# tenere-controller-rev-C.net
KiCad netlist of a schematic drawn in EAGLE
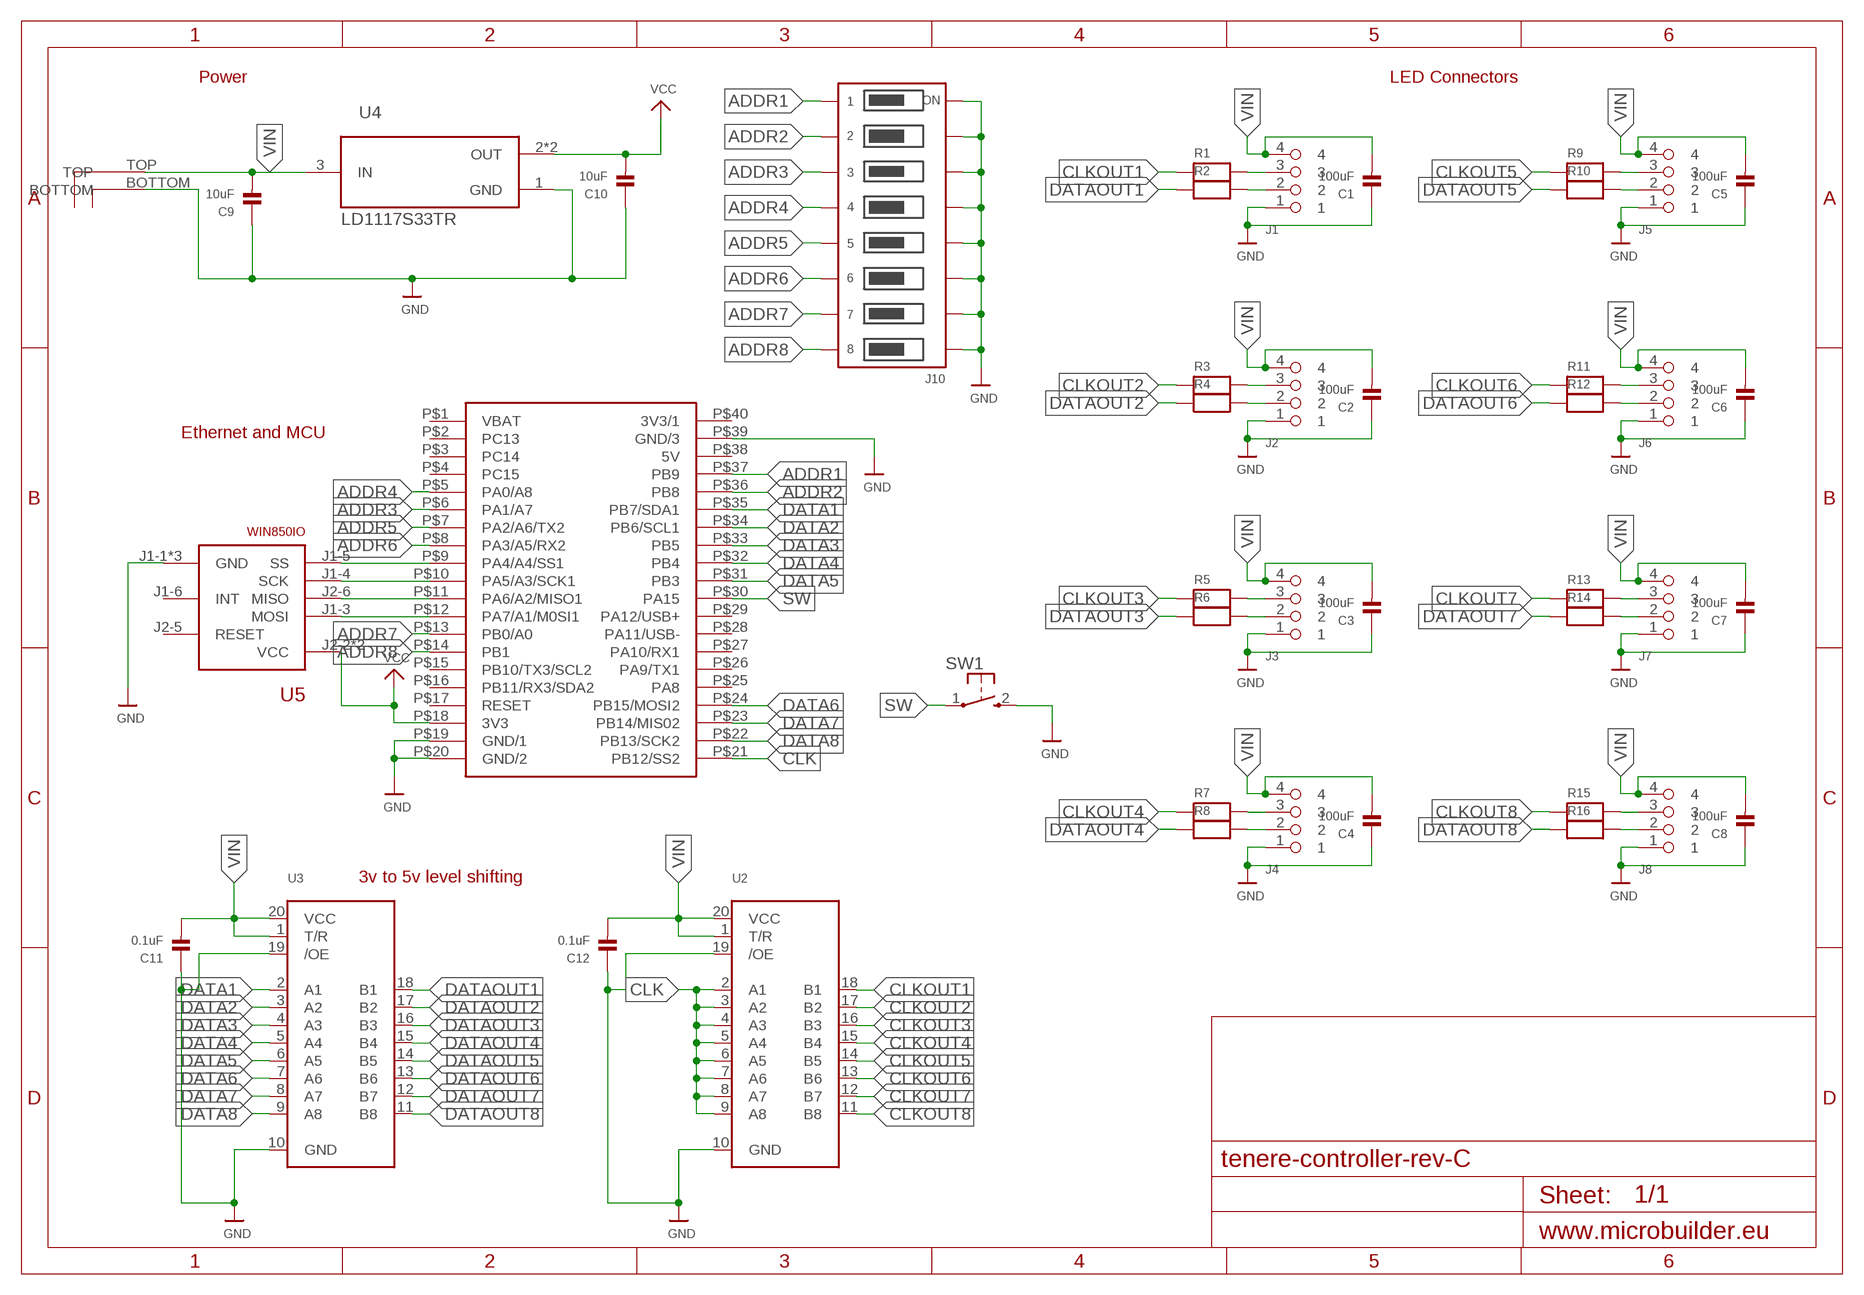
[diagram p0: schematic, sheet 1]

(export (version "E")
  (design (tool "Eeschema 10.0.6"))
  (components
    (comp (ref "C1")
      (value "100uF")
      (footprint "eagle-import:1206")
      (libsource (lib "eagle-import") (part "CAP_CERAMIC1206"))
    )
    (comp (ref "C2")
      (value "100uF")
      (footprint "eagle-import:1206")
      (libsource (lib "eagle-import") (part "CAP_CERAMIC1206"))
    )
    (comp (ref "C3")
      (value "100uF")
      (footprint "eagle-import:1206")
      (libsource (lib "eagle-import") (part "CAP_CERAMIC1206"))
    )
    (comp (ref "C4")
      (value "100uF")
      (footprint "eagle-import:1206")
      (libsource (lib "eagle-import") (part "CAP_CERAMIC1206"))
    )
    (comp (ref "C5")
      (value "100uF")
      (footprint "eagle-import:1206")
      (libsource (lib "eagle-import") (part "CAP_CERAMIC1206"))
    )
    (comp (ref "C6")
      (value "100uF")
      (footprint "eagle-import:1206")
      (libsource (lib "eagle-import") (part "CAP_CERAMIC1206"))
    )
    (comp (ref "C7")
      (value "100uF")
      (footprint "eagle-import:1206")
      (libsource (lib "eagle-import") (part "CAP_CERAMIC1206"))
    )
    (comp (ref "C8")
      (value "100uF")
      (footprint "eagle-import:1206")
      (libsource (lib "eagle-import") (part "CAP_CERAMIC1206"))
    )
    (comp (ref "C9")
      (value "10uF")
      (footprint "eagle-import:0603")
      (libsource (lib "eagle-import") (part "CAP_CERAMIC0603"))
    )
    (comp (ref "C10")
      (value "10uF")
      (footprint "eagle-import:0603")
      (libsource (lib "eagle-import") (part "CAP_CERAMIC0603"))
    )
    (comp (ref "C11")
      (value "0.1uF")
      (footprint "eagle-import:0603")
      (libsource (lib "eagle-import") (part "CAP_CERAMIC0603"))
    )
    (comp (ref "C12")
      (value "0.1uF")
      (footprint "eagle-import:0603")
      (libsource (lib "eagle-import") (part "CAP_CERAMIC0603"))
    )
    (comp (ref "J1")
      (value "MICROFIT3")
      (footprint "eagle-import:43650-0400")
      (libsource (lib "eagle-import") (part "MICROFIT3"))
    )
    (comp (ref "J2")
      (value "MICROFIT3")
      (footprint "eagle-import:43650-0400")
      (libsource (lib "eagle-import") (part "MICROFIT3"))
    )
    (comp (ref "J3")
      (value "MICROFIT3")
      (footprint "eagle-import:43650-0400")
      (libsource (lib "eagle-import") (part "MICROFIT3"))
    )
    (comp (ref "J4")
      (value "MICROFIT3")
      (footprint "eagle-import:43650-0400")
      (libsource (lib "eagle-import") (part "MICROFIT3"))
    )
    (comp (ref "J5")
      (value "MICROFIT3")
      (footprint "eagle-import:43650-0400")
      (libsource (lib "eagle-import") (part "MICROFIT3"))
    )
    (comp (ref "J6")
      (value "MICROFIT3")
      (footprint "eagle-import:43650-0400")
      (libsource (lib "eagle-import") (part "MICROFIT3"))
    )
    (comp (ref "J7")
      (value "MICROFIT3")
      (footprint "eagle-import:43650-0400")
      (libsource (lib "eagle-import") (part "MICROFIT3"))
    )
    (comp (ref "J8")
      (value "MICROFIT3")
      (footprint "eagle-import:43650-0400")
      (libsource (lib "eagle-import") (part "MICROFIT3"))
    )
    (comp (ref "J9")
      (value "POWERPOLE-2V")
      (footprint "eagle-import:POWERPOLE_STACKED")
      (libsource (lib "eagle-import") (part "POWERPOLE-2V"))
    )
    (comp (ref "J10")
      (value "DIP-SWITCH-8PIN")
      (footprint "eagle-import:BPA08B")
      (libsource (lib "eagle-import") (part "DIP-SWITCH-8PIN"))
    )
    (comp (ref "R1")
      (value "RESISTOR0603")
      (footprint "eagle-import:0603")
      (libsource (lib "eagle-import") (part "RESISTOR0603"))
    )
    (comp (ref "R2")
      (value "RESISTOR0603")
      (footprint "eagle-import:0603")
      (libsource (lib "eagle-import") (part "RESISTOR0603"))
    )
    (comp (ref "R3")
      (value "RESISTOR0603")
      (footprint "eagle-import:0603")
      (libsource (lib "eagle-import") (part "RESISTOR0603"))
    )
    (comp (ref "R4")
      (value "RESISTOR0603")
      (footprint "eagle-import:0603")
      (libsource (lib "eagle-import") (part "RESISTOR0603"))
    )
    (comp (ref "R5")
      (value "RESISTOR0603")
      (footprint "eagle-import:0603")
      (libsource (lib "eagle-import") (part "RESISTOR0603"))
    )
    (comp (ref "R6")
      (value "RESISTOR0603")
      (footprint "eagle-import:0603")
      (libsource (lib "eagle-import") (part "RESISTOR0603"))
    )
    (comp (ref "R7")
      (value "RESISTOR0603")
      (footprint "eagle-import:0603")
      (libsource (lib "eagle-import") (part "RESISTOR0603"))
    )
    (comp (ref "R8")
      (value "RESISTOR0603")
      (footprint "eagle-import:0603")
      (libsource (lib "eagle-import") (part "RESISTOR0603"))
    )
    (comp (ref "R9")
      (value "RESISTOR0603")
      (footprint "eagle-import:0603")
      (libsource (lib "eagle-import") (part "RESISTOR0603"))
    )
    (comp (ref "R10")
      (value "RESISTOR0603")
      (footprint "eagle-import:0603")
      (libsource (lib "eagle-import") (part "RESISTOR0603"))
    )
    (comp (ref "R11")
      (value "RESISTOR0603")
      (footprint "eagle-import:0603")
      (libsource (lib "eagle-import") (part "RESISTOR0603"))
    )
    (comp (ref "R12")
      (value "RESISTOR0603")
      (footprint "eagle-import:0603")
      (libsource (lib "eagle-import") (part "RESISTOR0603"))
    )
    (comp (ref "R13")
      (value "RESISTOR0603")
      (footprint "eagle-import:0603")
      (libsource (lib "eagle-import") (part "RESISTOR0603"))
    )
    (comp (ref "R14")
      (value "RESISTOR0603")
      (footprint "eagle-import:0603")
      (libsource (lib "eagle-import") (part "RESISTOR0603"))
    )
    (comp (ref "R15")
      (value "RESISTOR0603")
      (footprint "eagle-import:0603")
      (libsource (lib "eagle-import") (part "RESISTOR0603"))
    )
    (comp (ref "R16")
      (value "RESISTOR0603")
      (footprint "eagle-import:0603")
      (libsource (lib "eagle-import") (part "RESISTOR0603"))
    )
    (comp (ref "SW1")
      (value "TACTILE-SWITCH-1825027")
      (footprint "eagle-import:1825027")
      (libsource (lib "eagle-import") (part "TACTILE-SWITCH-1825027"))
    )
    (comp (ref "U1")
      (value "BLUEPILL")
      (footprint "eagle-import:40-DIP-BLUE-PIL")
      (libsource (lib "eagle-import") (part "BLUEPILL"))
    )
    (comp (ref "U2")
      (value "74LCX245")
      (footprint "eagle-import:TSSOP20")
      (libsource (lib "eagle-import") (part "74LCX245"))
    )
    (comp (ref "U3")
      (value "74LCX245")
      (footprint "eagle-import:TSSOP20")
      (libsource (lib "eagle-import") (part "74LCX245"))
    )
    (comp (ref "U4")
      (value "LD1117S33TR")
      (footprint "eagle-import:LD1117S33TR_SOT230P700X180-4N")
      (fields (field (name "MANUFACTURER") "ST Microelectronics"))
      (libsource (lib "eagle-import") (part "LD1117S33TR"))
    )
    (comp (ref "U5")
      (value "WIN850IO")
      (footprint "eagle-import:WIZ850IO")
      (libsource (lib "eagle-import") (part "WIN850IO"))
    )
  )
  (nets
    (net (code "1") (name "ADDR1") (class "Default")
      (node (ref "J10") (pin "1'") (pinfunction "1B_1'") (pintype "bidirectional"))
      (node (ref "U1") (pin "P$37") (pinfunction "PB9_P$37") (pintype "bidirectional"))
    )
    (net (code "2") (name "ADDR2") (class "Default")
      (node (ref "J10") (pin "2'") (pinfunction "2B_2'") (pintype "bidirectional"))
      (node (ref "U1") (pin "P$36") (pinfunction "PB8_P$36") (pintype "bidirectional"))
    )
    (net (code "3") (name "ADDR3") (class "Default")
      (node (ref "J10") (pin "3'") (pinfunction "3B_3'") (pintype "bidirectional"))
      (node (ref "U1") (pin "P$6") (pinfunction "PA1/A7_P$6") (pintype "bidirectional"))
    )
    (net (code "4") (name "ADDR4") (class "Default")
      (node (ref "J10") (pin "4'") (pinfunction "4B_4'") (pintype "bidirectional"))
      (node (ref "U1") (pin "P$5") (pinfunction "PA0/A8_P$5") (pintype "bidirectional"))
    )
    (net (code "5") (name "ADDR5") (class "Default")
      (node (ref "J10") (pin "5'") (pinfunction "5B_5'") (pintype "bidirectional"))
      (node (ref "U1") (pin "P$7") (pinfunction "PA2/A6/TX2_P$7") (pintype "bidirectional"))
    )
    (net (code "6") (name "ADDR6") (class "Default")
      (node (ref "J10") (pin "6'") (pinfunction "6B_6'") (pintype "bidirectional"))
      (node (ref "U1") (pin "P$8") (pinfunction "PA3/A5/RX2_P$8") (pintype "bidirectional"))
    )
    (net (code "7") (name "ADDR7") (class "Default")
      (node (ref "J10") (pin "7'") (pinfunction "7B_7'") (pintype "bidirectional"))
      (node (ref "U1") (pin "P$13") (pinfunction "PB0/A0_P$13") (pintype "bidirectional"))
    )
    (net (code "8") (name "ADDR8") (class "Default")
      (node (ref "J10") (pin "8'") (pinfunction "8B_8'") (pintype "bidirectional"))
      (node (ref "U1") (pin "P$14") (pinfunction "PB1_P$14") (pintype "bidirectional"))
    )
    (net (code "9") (name "CLK") (class "Default")
      (node (ref "U1") (pin "P$21") (pinfunction "PB12/SS2_P$21") (pintype "bidirectional"))
      (node (ref "U2") (pin "2") (pinfunction "A1_2") (pintype "bidirectional"))
      (node (ref "U2") (pin "3") (pinfunction "A2_3") (pintype "bidirectional"))
      (node (ref "U2") (pin "4") (pinfunction "A3_4") (pintype "bidirectional"))
      (node (ref "U2") (pin "5") (pinfunction "A4_5") (pintype "bidirectional"))
      (node (ref "U2") (pin "6") (pinfunction "A5_6") (pintype "bidirectional"))
      (node (ref "U2") (pin "7") (pinfunction "A6_7") (pintype "bidirectional"))
      (node (ref "U2") (pin "8") (pinfunction "A7_8") (pintype "bidirectional"))
      (node (ref "U2") (pin "9") (pinfunction "A8_9") (pintype "bidirectional"))
    )
    (net (code "10") (name "CLKOUT1") (class "Default")
      (node (ref "R1") (pin "1") (pinfunction "1_1") (pintype "passive"))
      (node (ref "U2") (pin "18") (pinfunction "B1_18") (pintype "bidirectional"))
    )
    (net (code "11") (name "CLKOUT2") (class "Default")
      (node (ref "R3") (pin "1") (pinfunction "1_1") (pintype "passive"))
      (node (ref "U2") (pin "17") (pinfunction "B2_17") (pintype "bidirectional"))
    )
    (net (code "12") (name "CLKOUT3") (class "Default")
      (node (ref "R5") (pin "1") (pinfunction "1_1") (pintype "passive"))
      (node (ref "U2") (pin "16") (pinfunction "B3_16") (pintype "bidirectional"))
    )
    (net (code "13") (name "CLKOUT4") (class "Default")
      (node (ref "R7") (pin "1") (pinfunction "1_1") (pintype "passive"))
      (node (ref "U2") (pin "15") (pinfunction "B4_15") (pintype "bidirectional"))
    )
    (net (code "14") (name "CLKOUT5") (class "Default")
      (node (ref "R9") (pin "1") (pinfunction "1_1") (pintype "passive"))
      (node (ref "U2") (pin "14") (pinfunction "B5_14") (pintype "bidirectional"))
    )
    (net (code "15") (name "CLKOUT6") (class "Default")
      (node (ref "R11") (pin "1") (pinfunction "1_1") (pintype "passive"))
      (node (ref "U2") (pin "13") (pinfunction "B6_13") (pintype "bidirectional"))
    )
    (net (code "16") (name "CLKOUT7") (class "Default")
      (node (ref "R13") (pin "1") (pinfunction "1_1") (pintype "passive"))
      (node (ref "U2") (pin "12") (pinfunction "B7_12") (pintype "bidirectional"))
    )
    (net (code "17") (name "CLKOUT8") (class "Default")
      (node (ref "R15") (pin "1") (pinfunction "1_1") (pintype "passive"))
      (node (ref "U2") (pin "11") (pinfunction "B8_11") (pintype "bidirectional"))
    )
    (net (code "18") (name "DATA1") (class "Default")
      (node (ref "U1") (pin "P$35") (pinfunction "PB7/SDA1_P$35") (pintype "bidirectional"))
      (node (ref "U3") (pin "2") (pinfunction "A1_2") (pintype "bidirectional"))
    )
    (net (code "19") (name "DATA2") (class "Default")
      (node (ref "U1") (pin "P$34") (pinfunction "PB6/SCL1_P$34") (pintype "bidirectional"))
      (node (ref "U3") (pin "3") (pinfunction "A2_3") (pintype "bidirectional"))
    )
    (net (code "20") (name "DATA3") (class "Default")
      (node (ref "U1") (pin "P$33") (pinfunction "PB5_P$33") (pintype "bidirectional"))
      (node (ref "U3") (pin "4") (pinfunction "A3_4") (pintype "bidirectional"))
    )
    (net (code "21") (name "DATA4") (class "Default")
      (node (ref "U1") (pin "P$32") (pinfunction "PB4_P$32") (pintype "bidirectional"))
      (node (ref "U3") (pin "5") (pinfunction "A4_5") (pintype "bidirectional"))
    )
    (net (code "22") (name "DATA5") (class "Default")
      (node (ref "U1") (pin "P$31") (pinfunction "PB3_P$31") (pintype "bidirectional"))
      (node (ref "U3") (pin "6") (pinfunction "A5_6") (pintype "bidirectional"))
    )
    (net (code "23") (name "DATA6") (class "Default")
      (node (ref "U1") (pin "P$24") (pinfunction "PB15/MOSI2_P$24") (pintype "bidirectional"))
      (node (ref "U3") (pin "7") (pinfunction "A6_7") (pintype "bidirectional"))
    )
    (net (code "24") (name "DATA7") (class "Default")
      (node (ref "U1") (pin "P$23") (pinfunction "PB14/MIS02_P$23") (pintype "bidirectional"))
      (node (ref "U3") (pin "8") (pinfunction "A7_8") (pintype "bidirectional"))
    )
    (net (code "25") (name "DATA8") (class "Default")
      (node (ref "U1") (pin "P$22") (pinfunction "PB13/SCK2_P$22") (pintype "bidirectional"))
      (node (ref "U3") (pin "9") (pinfunction "A8_9") (pintype "bidirectional"))
    )
    (net (code "26") (name "DATAOUT1") (class "Default")
      (node (ref "R2") (pin "1") (pinfunction "1_1") (pintype "passive"))
      (node (ref "U3") (pin "18") (pinfunction "B1_18") (pintype "bidirectional"))
    )
    (net (code "27") (name "DATAOUT2") (class "Default")
      (node (ref "R4") (pin "1") (pinfunction "1_1") (pintype "passive"))
      (node (ref "U3") (pin "17") (pinfunction "B2_17") (pintype "bidirectional"))
    )
    (net (code "28") (name "DATAOUT3") (class "Default")
      (node (ref "R6") (pin "1") (pinfunction "1_1") (pintype "passive"))
      (node (ref "U3") (pin "16") (pinfunction "B3_16") (pintype "bidirectional"))
    )
    (net (code "29") (name "DATAOUT4") (class "Default")
      (node (ref "R8") (pin "1") (pinfunction "1_1") (pintype "passive"))
      (node (ref "U3") (pin "15") (pinfunction "B4_15") (pintype "bidirectional"))
    )
    (net (code "30") (name "DATAOUT5") (class "Default")
      (node (ref "R10") (pin "1") (pinfunction "1_1") (pintype "passive"))
      (node (ref "U3") (pin "14") (pinfunction "B5_14") (pintype "bidirectional"))
    )
    (net (code "31") (name "DATAOUT6") (class "Default")
      (node (ref "R12") (pin "1") (pinfunction "1_1") (pintype "passive"))
      (node (ref "U3") (pin "13") (pinfunction "B6_13") (pintype "bidirectional"))
    )
    (net (code "32") (name "DATAOUT7") (class "Default")
      (node (ref "R14") (pin "1") (pinfunction "1_1") (pintype "passive"))
      (node (ref "U3") (pin "12") (pinfunction "B7_12") (pintype "bidirectional"))
    )
    (net (code "33") (name "DATAOUT8") (class "Default")
      (node (ref "R16") (pin "1") (pinfunction "1_1") (pintype "passive"))
      (node (ref "U3") (pin "11") (pinfunction "B8_11") (pintype "bidirectional"))
    )
    (net (code "34") (name "GND") (class "Default")
      (node (ref "C1") (pin "1") (pinfunction "P$1_1") (pintype "passive"))
      (node (ref "C10") (pin "1") (pinfunction "P$1_1") (pintype "passive"))
      (node (ref "C11") (pin "1") (pinfunction "P$1_1") (pintype "passive"))
      (node (ref "C12") (pin "1") (pinfunction "P$1_1") (pintype "passive"))
      (node (ref "C2") (pin "1") (pinfunction "P$1_1") (pintype "passive"))
      (node (ref "C3") (pin "1") (pinfunction "P$1_1") (pintype "passive"))
      (node (ref "C4") (pin "1") (pinfunction "P$1_1") (pintype "passive"))
      (node (ref "C5") (pin "1") (pinfunction "P$1_1") (pintype "passive"))
      (node (ref "C6") (pin "1") (pinfunction "P$1_1") (pintype "passive"))
      (node (ref "C7") (pin "1") (pinfunction "P$1_1") (pintype "passive"))
      (node (ref "C8") (pin "1") (pinfunction "P$1_1") (pintype "passive"))
      (node (ref "C9") (pin "1") (pinfunction "P$1_1") (pintype "passive"))
      (node (ref "J1") (pin "1") (pinfunction "1_1") (pintype "bidirectional"))
      (node (ref "J10") (pin "1") (pinfunction "1A_1") (pintype "bidirectional"))
      (node (ref "J10") (pin "2") (pinfunction "2A_2") (pintype "bidirectional"))
      (node (ref "J10") (pin "3") (pinfunction "3A_3") (pintype "bidirectional"))
      (node (ref "J10") (pin "4") (pinfunction "4A_4") (pintype "bidirectional"))
      (node (ref "J10") (pin "5") (pinfunction "5A_5") (pintype "bidirectional"))
      (node (ref "J10") (pin "6") (pinfunction "6A_6") (pintype "bidirectional"))
      (node (ref "J10") (pin "7") (pinfunction "7A_7") (pintype "bidirectional"))
      (node (ref "J10") (pin "8") (pinfunction "8A_8") (pintype "bidirectional"))
      (node (ref "J2") (pin "1") (pinfunction "1_1") (pintype "bidirectional"))
      (node (ref "J3") (pin "1") (pinfunction "1_1") (pintype "bidirectional"))
      (node (ref "J4") (pin "1") (pinfunction "1_1") (pintype "bidirectional"))
      (node (ref "J5") (pin "1") (pinfunction "1_1") (pintype "bidirectional"))
      (node (ref "J6") (pin "1") (pinfunction "1_1") (pintype "bidirectional"))
      (node (ref "J7") (pin "1") (pinfunction "1_1") (pintype "bidirectional"))
      (node (ref "J8") (pin "1") (pinfunction "1_1") (pintype "bidirectional"))
      (node (ref "J9") (pin "BOTTOM") (pinfunction "BOTTOM_BOTTOM") (pintype "bidirectional"))
      (node (ref "SW1") (pin "2") (pinfunction "3_2") (pintype "passive"))
      (node (ref "U1") (pin "P$19") (pinfunction "GND/1_P$19") (pintype "bidirectional"))
      (node (ref "U1") (pin "P$20") (pinfunction "GND/2_P$20") (pintype "bidirectional"))
      (node (ref "U1") (pin "P$39") (pinfunction "GND/3_P$39") (pintype "bidirectional"))
      (node (ref "U2") (pin "10") (pinfunction "GND_10") (pintype "bidirectional"))
      (node (ref "U2") (pin "19") (pinfunction "/OE_19") (pintype "bidirectional"))
      (node (ref "U3") (pin "10") (pinfunction "GND_10") (pintype "bidirectional"))
      (node (ref "U3") (pin "19") (pinfunction "/OE_19") (pintype "bidirectional"))
      (node (ref "U4") (pin "1") (pinfunction "GND_1") (pintype "power_in"))
      (node (ref "U5") (pin "J1-1") (pinfunction "GND_J1-1") (pintype "bidirectional"))
      (node (ref "U5") (pin "J1-2") (pinfunction "GND_J1-2") (pintype "bidirectional"))
      (node (ref "U5") (pin "J2-1") (pinfunction "GND_J2-1") (pintype "bidirectional"))
    )
    (net (code "35") (name "Net-(J1-Pad2)") (class "Default")
      (node (ref "J1") (pin "2") (pinfunction "2_2") (pintype "bidirectional"))
      (node (ref "R2") (pin "2") (pinfunction "2_2") (pintype "passive"))
    )
    (net (code "36") (name "Net-(J1-Pad3)") (class "Default")
      (node (ref "J1") (pin "3") (pinfunction "3_3") (pintype "bidirectional"))
      (node (ref "R1") (pin "2") (pinfunction "2_2") (pintype "passive"))
    )
    (net (code "37") (name "Net-(J2-Pad2)") (class "Default")
      (node (ref "J2") (pin "2") (pinfunction "2_2") (pintype "bidirectional"))
      (node (ref "R4") (pin "2") (pinfunction "2_2") (pintype "passive"))
    )
    (net (code "38") (name "Net-(J2-Pad3)") (class "Default")
      (node (ref "J2") (pin "3") (pinfunction "3_3") (pintype "bidirectional"))
      (node (ref "R3") (pin "2") (pinfunction "2_2") (pintype "passive"))
    )
    (net (code "39") (name "Net-(J3-Pad2)") (class "Default")
      (node (ref "J3") (pin "2") (pinfunction "2_2") (pintype "bidirectional"))
      (node (ref "R6") (pin "2") (pinfunction "2_2") (pintype "passive"))
    )
    (net (code "40") (name "Net-(J3-Pad3)") (class "Default")
      (node (ref "J3") (pin "3") (pinfunction "3_3") (pintype "bidirectional"))
      (node (ref "R5") (pin "2") (pinfunction "2_2") (pintype "passive"))
    )
    (net (code "41") (name "Net-(J4-Pad2)") (class "Default")
      (node (ref "J4") (pin "2") (pinfunction "2_2") (pintype "bidirectional"))
      (node (ref "R8") (pin "2") (pinfunction "2_2") (pintype "passive"))
    )
    (net (code "42") (name "Net-(J4-Pad3)") (class "Default")
      (node (ref "J4") (pin "3") (pinfunction "3_3") (pintype "bidirectional"))
      (node (ref "R7") (pin "2") (pinfunction "2_2") (pintype "passive"))
    )
    (net (code "43") (name "Net-(J5-Pad2)") (class "Default")
      (node (ref "J5") (pin "2") (pinfunction "2_2") (pintype "bidirectional"))
      (node (ref "R10") (pin "2") (pinfunction "2_2") (pintype "passive"))
    )
    (net (code "44") (name "Net-(J5-Pad3)") (class "Default")
      (node (ref "J5") (pin "3") (pinfunction "3_3") (pintype "bidirectional"))
      (node (ref "R9") (pin "2") (pinfunction "2_2") (pintype "passive"))
    )
    (net (code "45") (name "Net-(J6-Pad2)") (class "Default")
      (node (ref "J6") (pin "2") (pinfunction "2_2") (pintype "bidirectional"))
      (node (ref "R12") (pin "2") (pinfunction "2_2") (pintype "passive"))
    )
    (net (code "46") (name "Net-(J6-Pad3)") (class "Default")
      (node (ref "J6") (pin "3") (pinfunction "3_3") (pintype "bidirectional"))
      (node (ref "R11") (pin "2") (pinfunction "2_2") (pintype "passive"))
    )
    (net (code "47") (name "Net-(J7-Pad2)") (class "Default")
      (node (ref "J7") (pin "2") (pinfunction "2_2") (pintype "bidirectional"))
      (node (ref "R14") (pin "2") (pinfunction "2_2") (pintype "passive"))
    )
    (net (code "48") (name "Net-(J7-Pad3)") (class "Default")
      (node (ref "J7") (pin "3") (pinfunction "3_3") (pintype "bidirectional"))
      (node (ref "R13") (pin "2") (pinfunction "2_2") (pintype "passive"))
    )
    (net (code "49") (name "Net-(J8-Pad2)") (class "Default")
      (node (ref "J8") (pin "2") (pinfunction "2_2") (pintype "bidirectional"))
      (node (ref "R16") (pin "2") (pinfunction "2_2") (pintype "passive"))
    )
    (net (code "50") (name "Net-(J8-Pad3)") (class "Default")
      (node (ref "J8") (pin "3") (pinfunction "3_3") (pintype "bidirectional"))
      (node (ref "R15") (pin "2") (pinfunction "2_2") (pintype "passive"))
    )
    (net (code "51") (name "Net-(U1-PA4{slash}A4{slash}SS1)") (class "Default")
      (node (ref "U1") (pin "P$9") (pinfunction "PA4/A4/SS1_P$9") (pintype "bidirectional"))
      (node (ref "U5") (pin "J1-5") (pinfunction "SS_J1-5") (pintype "bidirectional"))
    )
    (net (code "52") (name "Net-(U1-PA5{slash}A3{slash}SCK1)") (class "Default")
      (node (ref "U1") (pin "P$10") (pinfunction "PA5/A3/SCK1_P$10") (pintype "bidirectional"))
      (node (ref "U5") (pin "J1-4") (pinfunction "SCK_J1-4") (pintype "bidirectional"))
    )
    (net (code "53") (name "Net-(U1-PA6{slash}A2{slash}MISO1)") (class "Default")
      (node (ref "U1") (pin "P$11") (pinfunction "PA6/A2/MISO1_P$11") (pintype "bidirectional"))
      (node (ref "U5") (pin "J2-6") (pinfunction "MISO_J2-6") (pintype "bidirectional"))
    )
    (net (code "54") (name "Net-(U1-PA7{slash}A1{slash}M0SI1)") (class "Default")
      (node (ref "U1") (pin "P$12") (pinfunction "PA7/A1/M0SI1_P$12") (pintype "bidirectional"))
      (node (ref "U5") (pin "J1-3") (pinfunction "MOSI_J1-3") (pintype "bidirectional"))
    )
    (net (code "55") (name "SW") (class "Default")
      (node (ref "SW1") (pin "1") (pinfunction "1_1") (pintype "passive"))
      (node (ref "U1") (pin "P$30") (pinfunction "PA15_P$30") (pintype "bidirectional"))
    )
    (net (code "56") (name "VCC") (class "Default")
      (node (ref "C10") (pin "2") (pinfunction "P$2_2") (pintype "passive"))
      (node (ref "U1") (pin "P$18") (pinfunction "3V3_P$18") (pintype "bidirectional"))
      (node (ref "U4") (pin "2") (pinfunction "OUT_2") (pintype "output"))
      (node (ref "U4") (pin "4") (pinfunction "OUT_4") (pintype "output"))
      (node (ref "U5") (pin "J2-2") (pinfunction "VCC_J2-2") (pintype "bidirectional"))
      (node (ref "U5") (pin "J2-3") (pinfunction "VCC_J2-3") (pintype "bidirectional"))
    )
    (net (code "57") (name "VIN") (class "Default")
      (node (ref "C1") (pin "2") (pinfunction "P$2_2") (pintype "passive"))
      (node (ref "C11") (pin "2") (pinfunction "P$2_2") (pintype "passive"))
      (node (ref "C12") (pin "2") (pinfunction "P$2_2") (pintype "passive"))
      (node (ref "C2") (pin "2") (pinfunction "P$2_2") (pintype "passive"))
      (node (ref "C3") (pin "2") (pinfunction "P$2_2") (pintype "passive"))
      (node (ref "C4") (pin "2") (pinfunction "P$2_2") (pintype "passive"))
      (node (ref "C5") (pin "2") (pinfunction "P$2_2") (pintype "passive"))
      (node (ref "C6") (pin "2") (pinfunction "P$2_2") (pintype "passive"))
      (node (ref "C7") (pin "2") (pinfunction "P$2_2") (pintype "passive"))
      (node (ref "C8") (pin "2") (pinfunction "P$2_2") (pintype "passive"))
      (node (ref "C9") (pin "2") (pinfunction "P$2_2") (pintype "passive"))
      (node (ref "J1") (pin "4") (pinfunction "4_4") (pintype "bidirectional"))
      (node (ref "J2") (pin "4") (pinfunction "4_4") (pintype "bidirectional"))
      (node (ref "J3") (pin "4") (pinfunction "4_4") (pintype "bidirectional"))
      (node (ref "J4") (pin "4") (pinfunction "4_4") (pintype "bidirectional"))
      (node (ref "J5") (pin "4") (pinfunction "4_4") (pintype "bidirectional"))
      (node (ref "J6") (pin "4") (pinfunction "4_4") (pintype "bidirectional"))
      (node (ref "J7") (pin "4") (pinfunction "4_4") (pintype "bidirectional"))
      (node (ref "J8") (pin "4") (pinfunction "4_4") (pintype "bidirectional"))
      (node (ref "J9") (pin "TOP") (pinfunction "TOP_TOP") (pintype "bidirectional"))
      (node (ref "U2") (pin "1") (pinfunction "T/R_1") (pintype "bidirectional"))
      (node (ref "U2") (pin "20") (pinfunction "VCC_20") (pintype "bidirectional"))
      (node (ref "U3") (pin "1") (pinfunction "T/R_1") (pintype "bidirectional"))
      (node (ref "U3") (pin "20") (pinfunction "VCC_20") (pintype "bidirectional"))
      (node (ref "U4") (pin "3") (pinfunction "IN_3") (pintype "input"))
    )
    (net (code "58") (name "unconnected-(U1-3V3{slash}1-PadP$40)") (class "Default")
      (node (ref "U1") (pin "P$40") (pinfunction "3V3/1_P$40") (pintype "bidirectional"))
    )
    (net (code "59") (name "unconnected-(U1-5V-PadP$38)") (class "Default")
      (node (ref "U1") (pin "P$38") (pinfunction "5V_P$38") (pintype "bidirectional"))
    )
    (net (code "60") (name "unconnected-(U1-PA8-PadP$25)") (class "Default")
      (node (ref "U1") (pin "P$25") (pinfunction "PA8_P$25") (pintype "bidirectional"))
    )
    (net (code "61") (name "unconnected-(U1-PA9{slash}TX1-PadP$26)") (class "Default")
      (node (ref "U1") (pin "P$26") (pinfunction "PA9/TX1_P$26") (pintype "bidirectional"))
    )
    (net (code "62") (name "unconnected-(U1-PA10{slash}RX1-PadP$27)") (class "Default")
      (node (ref "U1") (pin "P$27") (pinfunction "PA10/RX1_P$27") (pintype "bidirectional"))
    )
    (net (code "63") (name "unconnected-(U1-PA11{slash}USB--PadP$28)") (class "Default")
      (node (ref "U1") (pin "P$28") (pinfunction "PA11/USB-_P$28") (pintype "bidirectional"))
    )
    (net (code "64") (name "unconnected-(U1-PA12{slash}USB+-PadP$29)") (class "Default")
      (node (ref "U1") (pin "P$29") (pinfunction "PA12/USB+_P$29") (pintype "bidirectional"))
    )
    (net (code "65") (name "unconnected-(U1-PB10{slash}TX3{slash}SCL2-PadP$15)") (class "Default")
      (node (ref "U1") (pin "P$15") (pinfunction "PB10/TX3/SCL2_P$15") (pintype "bidirectional"))
    )
    (net (code "66") (name "unconnected-(U1-PB11{slash}RX3{slash}SDA2-PadP$16)") (class "Default")
      (node (ref "U1") (pin "P$16") (pinfunction "PB11/RX3/SDA2_P$16") (pintype "bidirectional"))
    )
    (net (code "67") (name "unconnected-(U1-PC13-PadP$2)") (class "Default")
      (node (ref "U1") (pin "P$2") (pinfunction "PC13_P$2") (pintype "bidirectional"))
    )
    (net (code "68") (name "unconnected-(U1-PC14-PadP$3)") (class "Default")
      (node (ref "U1") (pin "P$3") (pinfunction "PC14_P$3") (pintype "bidirectional"))
    )
    (net (code "69") (name "unconnected-(U1-PC15-PadP$4)") (class "Default")
      (node (ref "U1") (pin "P$4") (pinfunction "PC15_P$4") (pintype "bidirectional"))
    )
    (net (code "70") (name "unconnected-(U1-RESET-PadP$17)") (class "Default")
      (node (ref "U1") (pin "P$17") (pinfunction "RESET_P$17") (pintype "bidirectional"))
    )
    (net (code "71") (name "unconnected-(U1-VBAT-PadP$1)") (class "Default")
      (node (ref "U1") (pin "P$1") (pinfunction "VBAT_P$1") (pintype "bidirectional"))
    )
    (net (code "72") (name "unconnected-(U5-INT-PadJ1-6)") (class "Default")
      (node (ref "U5") (pin "J1-6") (pinfunction "INT_J1-6") (pintype "bidirectional"))
    )
    (net (code "73") (name "unconnected-(U5-RESET-PadJ2-5)") (class "Default")
      (node (ref "U5") (pin "J2-5") (pinfunction "RESET_J2-5") (pintype "bidirectional"))
    )
  )
)
